# Muleta.net
KiCad netlist of a schematic drawn in EAGLE
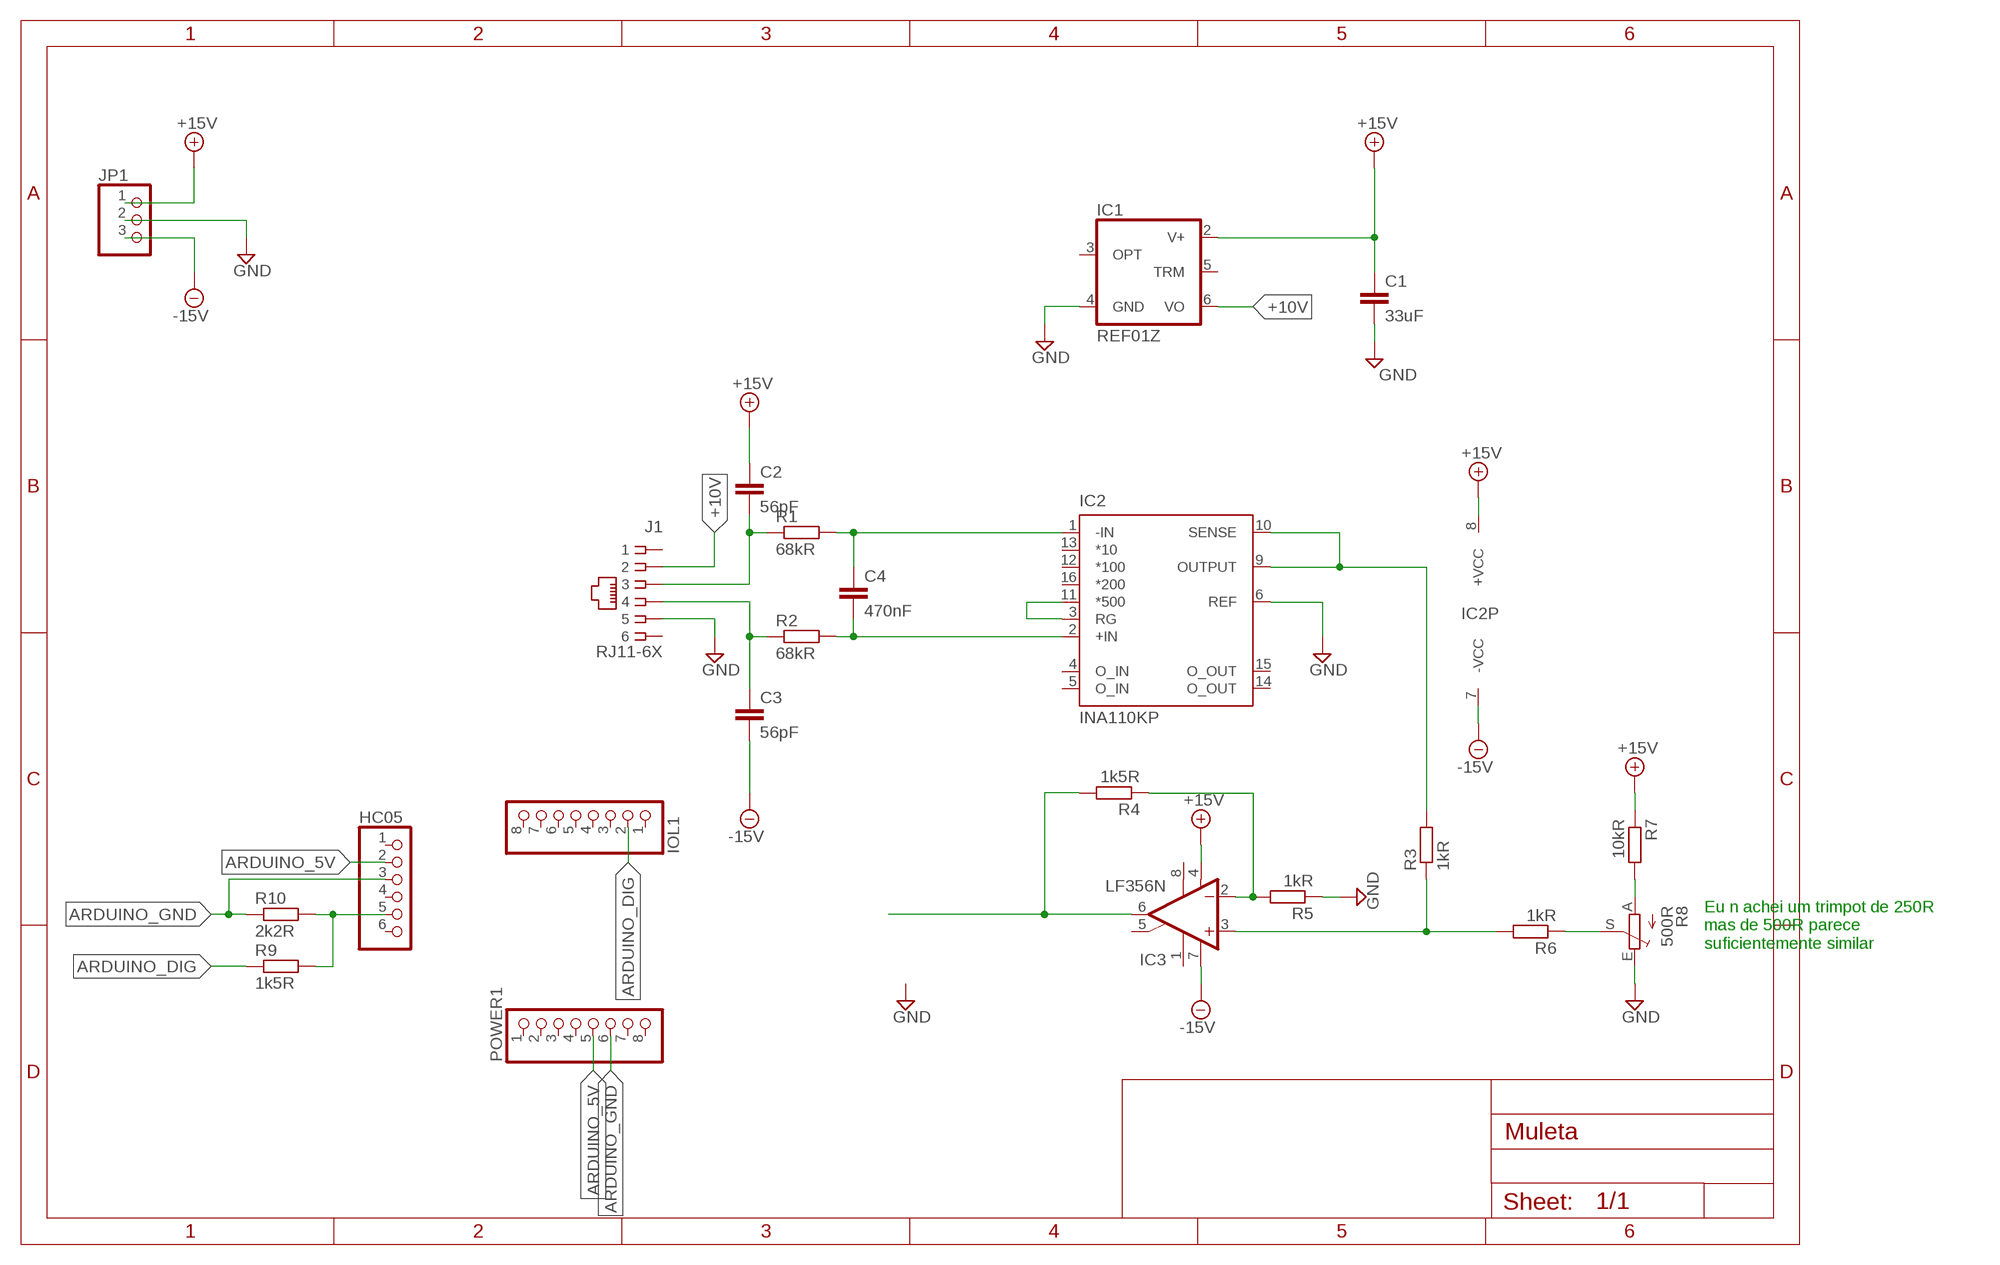
[diagram p0: schematic, sheet 1]

(export (version "E")
  (design (tool "Eeschema 10.0.6"))
  (components
    (comp (ref "C1")
      (value "33uF")
      (footprint "eagle-import:C2.5-3")
      (libsource (lib "eagle-import") (part "C2,5-3"))
    )
    (comp (ref "C2")
      (value "56pF")
      (footprint "eagle-import:C5B2.5")
      (libsource (lib "eagle-import") (part "C5/2.5"))
    )
    (comp (ref "C3")
      (value "56pF")
      (footprint "eagle-import:C5B2.5")
      (libsource (lib "eagle-import") (part "C5/2.5"))
    )
    (comp (ref "C4")
      (value "470nF")
      (footprint "eagle-import:C5B2.5")
      (libsource (lib "eagle-import") (part "C5/2.5"))
    )
    (comp (ref "HC05")
      (value "PINHD-1X6/90")
      (footprint "eagle-import:1X06_90")
      (libsource (lib "eagle-import") (part "PINHD-1X6/90"))
    )
    (comp (ref "IC1")
      (value "REF01Z")
      (footprint "eagle-import:DIL08")
      (libsource (lib "eagle-import") (part "REF01Z"))
    )
    (comp (ref "IC2")
      (value "INA110KP")
      (footprint "eagle-import:DIL16")
      (fields (field (name "MF") "TEXAS INSTRUMENTS"))
      (libsource (lib "eagle-import") (part "INA110PK"))
    )
    (comp (ref "IC3")
      (value "LF356N")
      (footprint "eagle-import:DIL08")
      (libsource (lib "eagle-import") (part "LF356N"))
    )
    (comp (ref "IOL1")
      (value "PINHD-1X8")
      (footprint "eagle-import:1X08")
      (libsource (lib "eagle-import") (part "PINHD-1X8"))
    )
    (comp (ref "J1")
      (value "RJ11-6X")
      (footprint "eagle-import:RJ11-NO_SHIELD")
      (libsource (lib "eagle-import") (part "RJ11-6X"))
    )
    (comp (ref "JP1")
      (value "PINHD-1X3")
      (footprint "eagle-import:1X03")
      (libsource (lib "eagle-import") (part "PINHD-1X3"))
    )
    (comp (ref "POWER1")
      (value "PINHD-1X8")
      (footprint "eagle-import:1X08")
      (libsource (lib "eagle-import") (part "pinhead_325_PINHD-1X8"))
    )
    (comp (ref "R1")
      (value "68kR")
      (footprint "eagle-import:0207_7")
      (libsource (lib "eagle-import") (part "R-EU_0207/7"))
    )
    (comp (ref "R2")
      (value "68kR")
      (footprint "eagle-import:0207_7")
      (libsource (lib "eagle-import") (part "R-EU_0207/7"))
    )
    (comp (ref "R3")
      (value "1kR")
      (footprint "eagle-import:0207_7")
      (libsource (lib "eagle-import") (part "R-EU_0207/7"))
    )
    (comp (ref "R4")
      (value "1k5R")
      (footprint "eagle-import:0207_7")
      (libsource (lib "eagle-import") (part "R-EU_0207/7"))
    )
    (comp (ref "R5")
      (value "1kR")
      (footprint "eagle-import:0207_7")
      (libsource (lib "eagle-import") (part "R-EU_0207/7"))
    )
    (comp (ref "R6")
      (value "1kR")
      (footprint "eagle-import:0207_7")
      (libsource (lib "eagle-import") (part "R-EU_0207/7"))
    )
    (comp (ref "R7")
      (value "10kR")
      (footprint "eagle-import:0207_7")
      (libsource (lib "eagle-import") (part "R-EU_0207/7"))
    )
    (comp (ref "R8")
      (value "500R")
      (footprint "eagle-import:B64Y")
      (libsource (lib "eagle-import") (part "TRIM_EU-B64Y"))
    )
    (comp (ref "R9")
      (value "1k5R")
      (footprint "eagle-import:0207_7")
      (libsource (lib "eagle-import") (part "R-EU_0207/7"))
    )
    (comp (ref "R10")
      (value "2k2R")
      (footprint "eagle-import:0207_7")
      (libsource (lib "eagle-import") (part "R-EU_0207/7"))
    )
  )
  (nets
    (net (code "1") (name "+10V") (class "Default")
      (node (ref "IC1") (pin "6") (pinfunction "VO_6") (pintype "output"))
      (node (ref "J1") (pin "2") (pinfunction "2_2") (pintype "passive"))
    )
    (net (code "2") (name "+15V") (class "Default")
      (node (ref "C1") (pin "1") (pinfunction "1_1") (pintype "passive"))
      (node (ref "C2") (pin "1") (pinfunction "1_1") (pintype "passive"))
      (node (ref "IC1") (pin "2") (pinfunction "V+_2") (pintype "power_in"))
      (node (ref "IC2") (pin "8") (pinfunction "+VCC_8") (pintype "power_in"))
      (node (ref "IC3") (pin "4") (pinfunction "V-_4") (pintype "power_in"))
      (node (ref "JP1") (pin "1") (pinfunction "1_1") (pintype "passive"))
      (node (ref "R7") (pin "1") (pinfunction "1_1") (pintype "passive"))
    )
    (net (code "3") (name "-15V") (class "Default")
      (node (ref "C3") (pin "2") (pinfunction "2_2") (pintype "passive"))
      (node (ref "IC2") (pin "7") (pinfunction "-VCC_7") (pintype "power_in"))
      (node (ref "IC3") (pin "7") (pinfunction "V+_7") (pintype "power_in"))
      (node (ref "JP1") (pin "3") (pinfunction "3_3") (pintype "passive"))
    )
    (net (code "4") (name "ARDUINO_5V") (class "Default")
      (node (ref "HC05") (pin "2") (pinfunction "2_2") (pintype "passive"))
      (node (ref "POWER1") (pin "5") (pinfunction "5_5") (pintype "passive"))
    )
    (net (code "5") (name "ARDUINO_DIG") (class "Default")
      (node (ref "IOL1") (pin "2") (pinfunction "2_2") (pintype "passive"))
      (node (ref "R9") (pin "1") (pinfunction "1_1") (pintype "passive"))
    )
    (net (code "6") (name "ARDUINO_GND") (class "Default")
      (node (ref "HC05") (pin "3") (pinfunction "3_3") (pintype "passive"))
      (node (ref "POWER1") (pin "6") (pinfunction "6_6") (pintype "passive"))
      (node (ref "R10") (pin "1") (pinfunction "1_1") (pintype "passive"))
    )
    (net (code "7") (name "GND") (class "Default")
      (node (ref "C1") (pin "2") (pinfunction "2_2") (pintype "passive"))
      (node (ref "IC1") (pin "4") (pinfunction "GND_4") (pintype "power_in"))
      (node (ref "IC2") (pin "6") (pinfunction "REF_6") (pintype "input"))
      (node (ref "J1") (pin "5") (pinfunction "5_5") (pintype "passive"))
      (node (ref "JP1") (pin "2") (pinfunction "2_2") (pintype "passive"))
      (node (ref "R5") (pin "1") (pinfunction "1_1") (pintype "passive"))
      (node (ref "R8") (pin "E") (pinfunction "E_E") (pintype "passive"))
    )
    (net (code "8") (name "Net-(C2-Pad2)") (class "Default")
      (node (ref "C2") (pin "2") (pinfunction "2_2") (pintype "passive"))
      (node (ref "J1") (pin "3") (pinfunction "3_3") (pintype "passive"))
      (node (ref "R1") (pin "1") (pinfunction "1_1") (pintype "passive"))
    )
    (net (code "9") (name "Net-(C3-Pad1)") (class "Default")
      (node (ref "C3") (pin "1") (pinfunction "1_1") (pintype "passive"))
      (node (ref "J1") (pin "4") (pinfunction "4_4") (pintype "passive"))
      (node (ref "R2") (pin "1") (pinfunction "1_1") (pintype "passive"))
    )
    (net (code "10") (name "Net-(HC05-Pad5)") (class "Default")
      (node (ref "HC05") (pin "5") (pinfunction "5_5") (pintype "passive"))
      (node (ref "R10") (pin "2") (pinfunction "2_2") (pintype "passive"))
      (node (ref "R9") (pin "2") (pinfunction "2_2") (pintype "passive"))
    )
    (net (code "11") (name "Net-(IC2A-*500)") (class "Default")
      (node (ref "IC2") (pin "11") (pinfunction "*500_11") (pintype "passive"))
      (node (ref "IC2") (pin "3") (pinfunction "RG_3") (pintype "passive"))
    )
    (net (code "12") (name "Net-(IC2A-+IN)") (class "Default")
      (node (ref "C4") (pin "2") (pinfunction "2_2") (pintype "passive"))
      (node (ref "IC2") (pin "2") (pinfunction "+IN_2") (pintype "input"))
      (node (ref "R2") (pin "2") (pinfunction "2_2") (pintype "passive"))
    )
    (net (code "13") (name "Net-(IC2A--IN)") (class "Default")
      (node (ref "C4") (pin "1") (pinfunction "1_1") (pintype "passive"))
      (node (ref "IC2") (pin "1") (pinfunction "-IN_1") (pintype "input"))
      (node (ref "R1") (pin "2") (pinfunction "2_2") (pintype "passive"))
    )
    (net (code "14") (name "Net-(IC2A-OUTPUT)") (class "Default")
      (node (ref "IC2") (pin "10") (pinfunction "SENSE_10") (pintype "input"))
      (node (ref "IC2") (pin "9") (pinfunction "OUTPUT_9") (pintype "output"))
      (node (ref "R3") (pin "2") (pinfunction "2_2") (pintype "passive"))
    )
    (net (code "15") (name "Net-(IC3-+IN)") (class "Default")
      (node (ref "IC3") (pin "3") (pinfunction "+IN_3") (pintype "input"))
      (node (ref "R3") (pin "1") (pinfunction "1_1") (pintype "passive"))
      (node (ref "R6") (pin "2") (pinfunction "2_2") (pintype "passive"))
    )
    (net (code "16") (name "Net-(IC3--IN)") (class "Default")
      (node (ref "IC3") (pin "2") (pinfunction "-IN_2") (pintype "input"))
      (node (ref "R4") (pin "1") (pinfunction "1_1") (pintype "passive"))
      (node (ref "R5") (pin "2") (pinfunction "2_2") (pintype "passive"))
    )
    (net (code "17") (name "Net-(IC3-OUT)") (class "Default")
      (node (ref "IC3") (pin "6") (pinfunction "OUT_6") (pintype "output"))
      (node (ref "R4") (pin "2") (pinfunction "2_2") (pintype "passive"))
    )
    (net (code "18") (name "Net-(R6-Pad1)") (class "Default")
      (node (ref "R6") (pin "1") (pinfunction "1_1") (pintype "passive"))
      (node (ref "R8") (pin "S") (pinfunction "S_S") (pintype "passive"))
    )
    (net (code "19") (name "Net-(R7-Pad2)") (class "Default")
      (node (ref "R7") (pin "2") (pinfunction "2_2") (pintype "passive"))
      (node (ref "R8") (pin "A") (pinfunction "A_A") (pintype "passive"))
    )
    (net (code "20") (name "unconnected-(HC05-Pad1)") (class "Default")
      (node (ref "HC05") (pin "1") (pinfunction "1_1") (pintype "passive"))
    )
    (net (code "21") (name "unconnected-(HC05-Pad4)") (class "Default")
      (node (ref "HC05") (pin "4") (pinfunction "4_4") (pintype "passive"))
    )
    (net (code "22") (name "unconnected-(HC05-Pad6)") (class "Default")
      (node (ref "HC05") (pin "6") (pinfunction "6_6") (pintype "passive"))
    )
    (net (code "23") (name "unconnected-(IC1-OPT-Pad3)") (class "Default")
      (node (ref "IC1") (pin "3") (pinfunction "OPT_3") (pintype "output"))
    )
    (net (code "24") (name "unconnected-(IC1-TRM-Pad5)") (class "Default")
      (node (ref "IC1") (pin "5") (pinfunction "TRM_5") (pintype "input"))
    )
    (net (code "25") (name "unconnected-(IC2A-*10-Pad13)") (class "Default")
      (node (ref "IC2") (pin "13") (pinfunction "*10_13") (pintype "passive"))
    )
    (net (code "26") (name "unconnected-(IC2A-*100-Pad12)") (class "Default")
      (node (ref "IC2") (pin "12") (pinfunction "*100_12") (pintype "passive"))
    )
    (net (code "27") (name "unconnected-(IC2A-*200-Pad16)") (class "Default")
      (node (ref "IC2") (pin "16") (pinfunction "*200_16") (pintype "passive"))
    )
    (net (code "28") (name "unconnected-(IC2A-O_IN-Pad4)") (class "Default")
      (node (ref "IC2") (pin "4") (pinfunction "O_IN_4") (pintype "passive"))
    )
    (net (code "29") (name "unconnected-(IC2A-O_IN-Pad5)") (class "Default")
      (node (ref "IC2") (pin "5") (pinfunction "O_IN_5") (pintype "passive"))
    )
    (net (code "30") (name "unconnected-(IC2A-O_OUT-Pad14)") (class "Default")
      (node (ref "IC2") (pin "14") (pinfunction "O_OUT_14") (pintype "passive"))
    )
    (net (code "31") (name "unconnected-(IC2A-O_OUT-Pad15)") (class "Default")
      (node (ref "IC2") (pin "15") (pinfunction "O_OUT_15") (pintype "passive"))
    )
    (net (code "32") (name "unconnected-(IC3-ON1-Pad1)") (class "Default")
      (node (ref "IC3") (pin "1") (pinfunction "ON1_1") (pintype "passive"))
    )
    (net (code "33") (name "unconnected-(IC3-ON2-Pad5)") (class "Default")
      (node (ref "IC3") (pin "5") (pinfunction "ON2_5") (pintype "passive"))
    )
    (net (code "34") (name "unconnected-(IC3-OPT-Pad8)") (class "Default")
      (node (ref "IC3") (pin "8") (pinfunction "OPT_8") (pintype "passive"))
    )
    (net (code "35") (name "unconnected-(IOL1-Pad1)") (class "Default")
      (node (ref "IOL1") (pin "1") (pinfunction "1_1") (pintype "passive"))
    )
    (net (code "36") (name "unconnected-(IOL1-Pad3)") (class "Default")
      (node (ref "IOL1") (pin "3") (pinfunction "3_3") (pintype "passive"))
    )
    (net (code "37") (name "unconnected-(IOL1-Pad4)") (class "Default")
      (node (ref "IOL1") (pin "4") (pinfunction "4_4") (pintype "passive"))
    )
    (net (code "38") (name "unconnected-(IOL1-Pad5)") (class "Default")
      (node (ref "IOL1") (pin "5") (pinfunction "5_5") (pintype "passive"))
    )
    (net (code "39") (name "unconnected-(IOL1-Pad6)") (class "Default")
      (node (ref "IOL1") (pin "6") (pinfunction "6_6") (pintype "passive"))
    )
    (net (code "40") (name "unconnected-(IOL1-Pad7)") (class "Default")
      (node (ref "IOL1") (pin "7") (pinfunction "7_7") (pintype "passive"))
    )
    (net (code "41") (name "unconnected-(IOL1-Pad8)") (class "Default")
      (node (ref "IOL1") (pin "8") (pinfunction "8_8") (pintype "passive"))
    )
    (net (code "42") (name "unconnected-(J1-Pad1)") (class "Default")
      (node (ref "J1") (pin "1") (pinfunction "1_1") (pintype "passive"))
    )
    (net (code "43") (name "unconnected-(J1-Pad6)") (class "Default")
      (node (ref "J1") (pin "6") (pinfunction "6_6") (pintype "passive"))
    )
    (net (code "44") (name "unconnected-(POWER1-Pad1)") (class "Default")
      (node (ref "POWER1") (pin "1") (pinfunction "1_1") (pintype "passive"))
    )
    (net (code "45") (name "unconnected-(POWER1-Pad2)") (class "Default")
      (node (ref "POWER1") (pin "2") (pinfunction "2_2") (pintype "passive"))
    )
    (net (code "46") (name "unconnected-(POWER1-Pad3)") (class "Default")
      (node (ref "POWER1") (pin "3") (pinfunction "3_3") (pintype "passive"))
    )
    (net (code "47") (name "unconnected-(POWER1-Pad4)") (class "Default")
      (node (ref "POWER1") (pin "4") (pinfunction "4_4") (pintype "passive"))
    )
    (net (code "48") (name "unconnected-(POWER1-Pad7)") (class "Default")
      (node (ref "POWER1") (pin "7") (pinfunction "7_7") (pintype "passive"))
    )
    (net (code "49") (name "unconnected-(POWER1-Pad8)") (class "Default")
      (node (ref "POWER1") (pin "8") (pinfunction "8_8") (pintype "passive"))
    )
  )
)
